# Mach_side_sch.net
KiCad netlist of a schematic drawn in Altium Designer
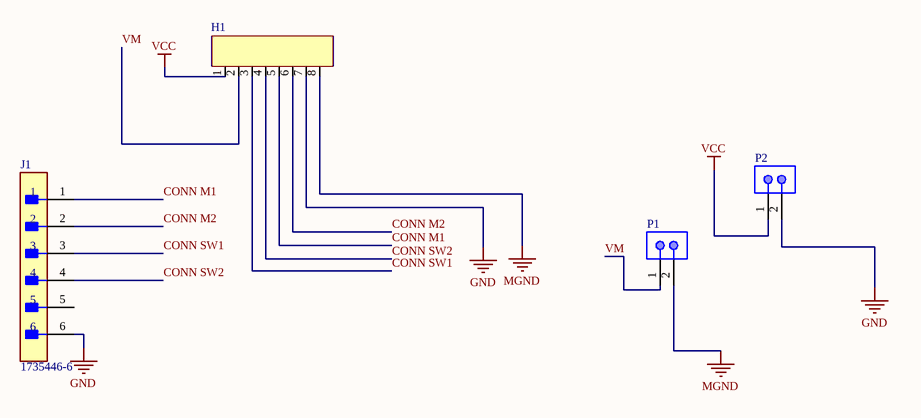
[diagram p0: Mach_side_sch.SchDoc]

(export (version "E")
  (design (tool "Eeschema 10.0.6"))
  (components
    (comp (ref "H1")
      (value "1747785-1")
      (footprint "1747785-1")
      (libsource (lib "SchLib18thNov(1747785-1 8 pin connector)(1)") (part "1747785-1"))
    )
    (comp (ref "J1")
      (value "1735446-6")
      (footprint "FP-1735446-6-MFG")
      (description "CONN HEADER VERT 6POS 2MM")
      (fields
        (field (name "MANUFACTURER") "TE")
        (field (name "OCTOPART") "https://octopart.com/1735446-6-te+connectivity-42205942")
      )
      (libsource (lib "Altium Content Vault") (part "f2cb566baf1c37ab5a3b8e90bbeafd6"))
    )
    (comp (ref "P1")
      (value "B2B-XH-A(LF)(SN)")
      (footprint "JST-B2B-XH-A_V")
      (fields (field (name "MANUFACTURER") "JST"))
      (libsource (lib "Altium Content Vault") (part "CN-1P-M-R2"))
    )
    (comp (ref "P2")
      (value "B2B-XH-A(LF)(SN)")
      (footprint "JST-B2B-XH-A_V")
      (fields (field (name "MANUFACTURER") "JST"))
      (libsource (lib "Altium Content Vault") (part "CN-1P-M-R2"))
    )
  )
  (nets
    (net (code "1") (name "/CONN M1") (class "Default")
      (node (ref "H1") (pin "5") (pinfunction "5_5") (pintype "passive"))
      (node (ref "J1") (pin "1") (pinfunction "1_1") (pintype "passive"))
    )
    (net (code "2") (name "/CONN M2") (class "Default")
      (node (ref "H1") (pin "6") (pinfunction "6_6") (pintype "passive"))
      (node (ref "J1") (pin "2") (pinfunction "2_2") (pintype "passive"))
    )
    (net (code "3") (name "/CONN SW1") (class "Default")
      (node (ref "H1") (pin "3") (pinfunction "3_3") (pintype "passive"))
      (node (ref "J1") (pin "3") (pinfunction "3_3") (pintype "passive"))
    )
    (net (code "4") (name "/CONN SW2") (class "Default")
      (node (ref "H1") (pin "4") (pinfunction "4_4") (pintype "passive"))
      (node (ref "J1") (pin "4") (pinfunction "4_4") (pintype "passive"))
    )
    (net (code "5") (name "/VM") (class "Default")
      (node (ref "H1") (pin "2") (pinfunction "2_2") (pintype "passive"))
      (node (ref "P1") (pin "1") (pinfunction "1_1") (pintype "passive"))
    )
    (net (code "6") (name "GND") (class "Default")
      (node (ref "H1") (pin "7") (pinfunction "7_7") (pintype "passive"))
      (node (ref "J1") (pin "6") (pinfunction "6_6") (pintype "passive"))
      (node (ref "P2") (pin "2") (pinfunction "2_2") (pintype "passive"))
    )
    (net (code "7") (name "MGND") (class "Default")
      (node (ref "H1") (pin "8") (pinfunction "8_8") (pintype "passive"))
      (node (ref "P1") (pin "2") (pinfunction "2_2") (pintype "passive"))
    )
    (net (code "8") (name "VCC") (class "Default")
      (node (ref "H1") (pin "1") (pinfunction "1_1") (pintype "passive"))
      (node (ref "P2") (pin "1") (pinfunction "1_1") (pintype "passive"))
    )
    (net (code "9") (name "unconnected-(J1-Pad5)") (class "Default")
      (node (ref "J1") (pin "5") (pinfunction "5_5") (pintype "passive"))
    )
  )
)
